# Temperature_Controller.net
KiCad netlist of a schematic drawn in Altium Designer
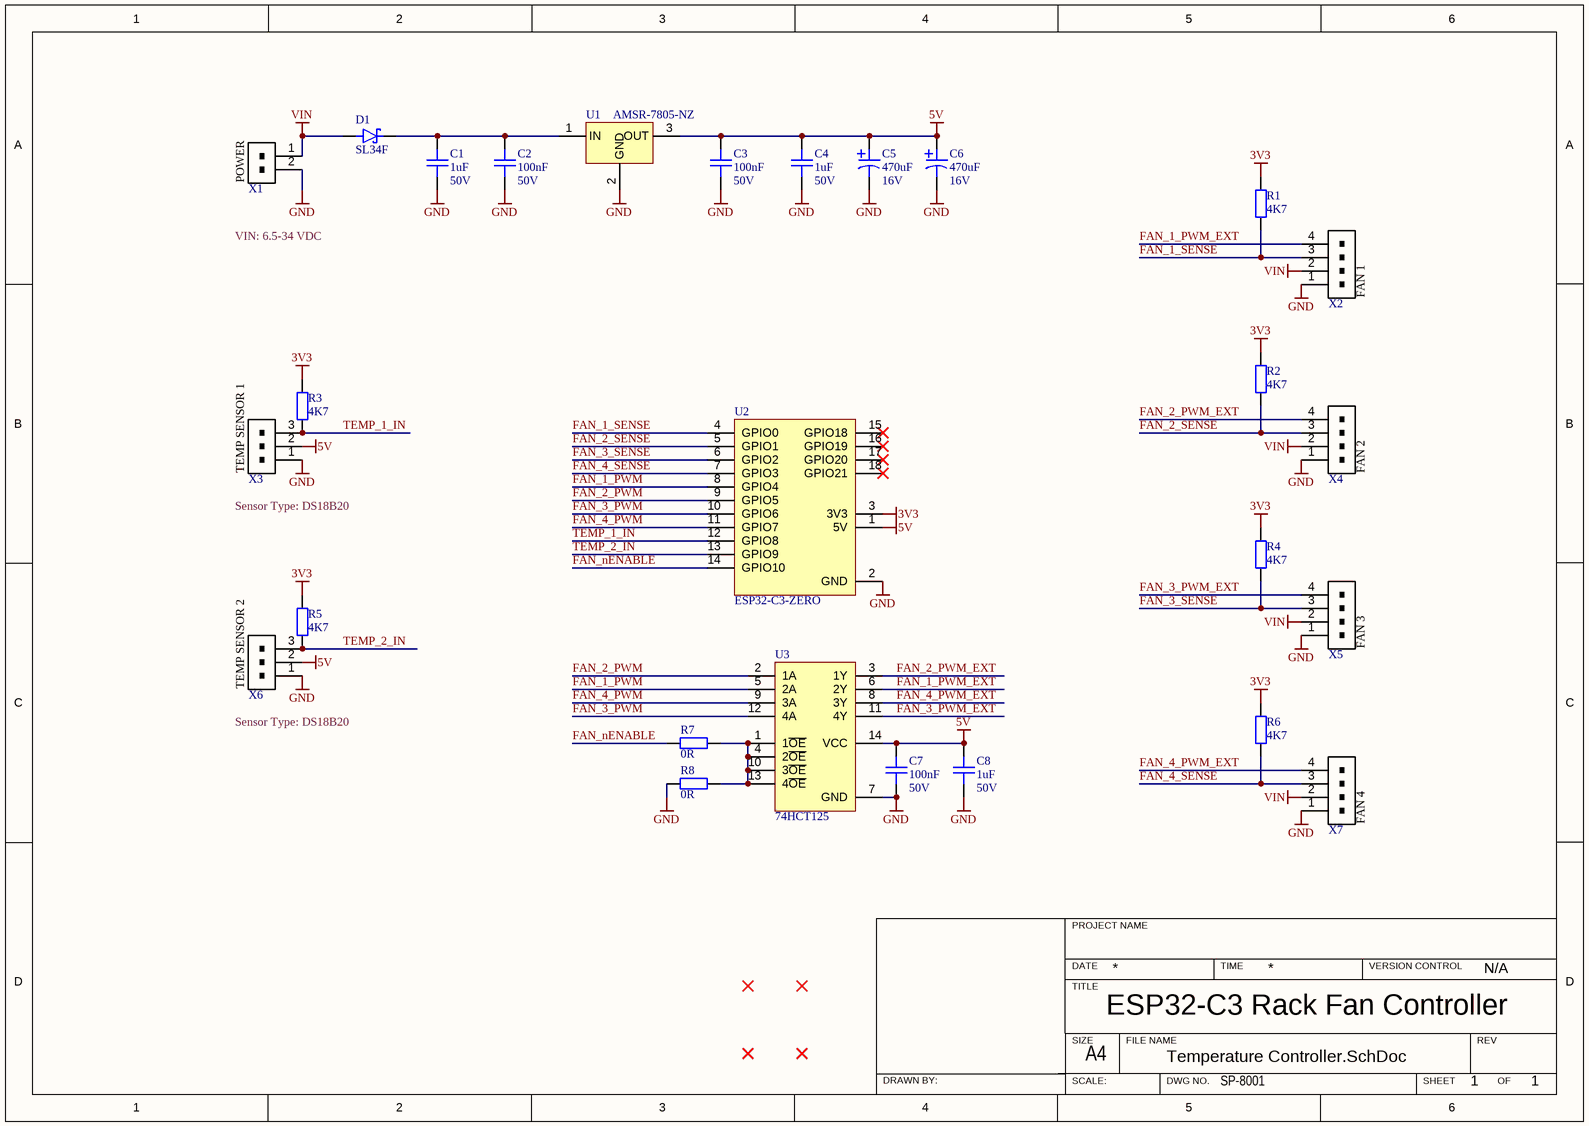
[diagram p0: Temperature Controller.SchDoc]

(export (version "E")
  (design (tool "Eeschema 10.0.6"))
  (components
    (comp (ref "C1")
      (value "1uF")
      (footprint "CAP-0805")
      (description "Capacitor Non-Polar")
      (fields (field (name "VOLTAGE") "50V") (field (name "TOLERANCE") "X7R"))
      (libsource (lib "ComponentDatabase") (part "CAP-0805"))
    )
    (comp (ref "C2")
      (value "100nF")
      (footprint "CAP-0805")
      (description "Capacitor Non-Polar")
      (fields (field (name "VOLTAGE") "50V") (field (name "TOLERANCE") "X7R"))
      (libsource (lib "ComponentDatabase") (part "CAP-0805"))
    )
    (comp (ref "C3")
      (value "100nF")
      (footprint "CAP-0805")
      (description "Capacitor Non-Polar")
      (fields (field (name "VOLTAGE") "50V") (field (name "TOLERANCE") "X7R"))
      (libsource (lib "ComponentDatabase") (part "CAP-0805"))
    )
    (comp (ref "C4")
      (value "1uF")
      (footprint "CAP-0805")
      (description "Capacitor Non-Polar")
      (fields (field (name "VOLTAGE") "50V") (field (name "TOLERANCE") "X7R"))
      (libsource (lib "ComponentDatabase") (part "CAP-0805"))
    )
    (comp (ref "C5")
      (value "470uF")
      (footprint "CAP-ELCO-SMD-FK1")
      (description "470uF 16V")
      (fields (field (name "VOLTAGE") "16V"))
      (libsource (lib "ComponentDatabase") (part "CAP-SMD-POL"))
    )
    (comp (ref "C6")
      (value "470uF")
      (footprint "CAP-ELCO-SMD-FK1")
      (description "470uF 16V")
      (fields (field (name "VOLTAGE") "16V"))
      (libsource (lib "ComponentDatabase") (part "CAP-SMD-POL"))
    )
    (comp (ref "C7")
      (value "100nF")
      (footprint "CAP-0805")
      (description "Capacitor Non-Polar")
      (fields (field (name "VOLTAGE") "50V") (field (name "TOLERANCE") "X7R"))
      (libsource (lib "ComponentDatabase") (part "CAP-0805"))
    )
    (comp (ref "C8")
      (value "1uF")
      (footprint "CAP-0805")
      (description "Capacitor Non-Polar")
      (fields (field (name "VOLTAGE") "50V") (field (name "TOLERANCE") "X7R"))
      (libsource (lib "ComponentDatabase") (part "CAP-0805"))
    )
    (comp (ref "D1")
      (value "SL34F")
      (footprint "D-SMAF")
      (description "3A 40V SCH.RECT. Vf=0.45V")
      (libsource (lib "ComponentDatabase") (part "D-SCHOTTKY"))
    )
    (comp (ref "MH1")
      (value "MECH-SCREW")
      (footprint "MECH-M3-LARGE-EMPTY-DOUBLE-SUPPORT")
      (description "M3, large ring, double support silkscreen")
      (libsource (lib "ComponentDatabase") (part "MECH-SCREW"))
    )
    (comp (ref "MH2")
      (value "MECH-SCREW")
      (footprint "MECH-M3-LARGE-EMPTY-DOUBLE-SUPPORT")
      (description "M3, large ring, double support silkscreen")
      (libsource (lib "ComponentDatabase") (part "MECH-SCREW"))
    )
    (comp (ref "MH3")
      (value "MECH-SCREW")
      (footprint "MECH-M3-LARGE-EMPTY-DOUBLE-SUPPORT")
      (description "M3, large ring, double support silkscreen")
      (libsource (lib "ComponentDatabase") (part "MECH-SCREW"))
    )
    (comp (ref "MH4")
      (value "MECH-SCREW")
      (footprint "MECH-M3-LARGE-EMPTY-DOUBLE-SUPPORT")
      (description "M3, large ring, double support silkscreen")
      (libsource (lib "ComponentDatabase") (part "MECH-SCREW"))
    )
    (comp (ref "R1")
      (value "4K7")
      (footprint "RES-0805")
      (description "Resistor")
      (libsource (lib "ComponentDatabase") (part "RES-0805"))
    )
    (comp (ref "R2")
      (value "4K7")
      (footprint "RES-0805")
      (description "Resistor")
      (libsource (lib "ComponentDatabase") (part "RES-0805"))
    )
    (comp (ref "R3")
      (value "4K7")
      (footprint "RES-0805")
      (description "Resistor")
      (libsource (lib "ComponentDatabase") (part "RES-0805"))
    )
    (comp (ref "R4")
      (value "4K7")
      (footprint "RES-0805")
      (description "Resistor")
      (libsource (lib "ComponentDatabase") (part "RES-0805"))
    )
    (comp (ref "R5")
      (value "4K7")
      (footprint "RES-0805")
      (description "Resistor")
      (libsource (lib "ComponentDatabase") (part "RES-0805"))
    )
    (comp (ref "R6")
      (value "4K7")
      (footprint "RES-0805")
      (description "Resistor")
      (libsource (lib "ComponentDatabase") (part "RES-0805"))
    )
    (comp (ref "R7")
      (value "0R")
      (footprint "RES-0805")
      (description "Resistor")
      (libsource (lib "") (part "RES-0805_1"))
    )
    (comp (ref "R8")
      (value "0R")
      (footprint "RES-0805")
      (description "Resistor")
      (libsource (lib "") (part "RES-0805_1"))
    )
    (comp (ref "U1")
      (value "AMSR-7805-NZ")
      (footprint "IC-AMS-7805")
      (description "Converter: DC/DC, 2.5W, Uin: 6.5-32V, Uout: 5VDC, Iout: 500mA")
      (libsource (lib "ComponentDatabase") (part "IC-LDO-AMSR-7805"))
    )
    (comp (ref "U2")
      (value "ESP32-C3-ZERO")
      (footprint "MOD-ESP32-C3-ZERO")
      (libsource (lib "ComponentDatabase") (part "MOD-ESP32-C3-ZERO"))
    )
    (comp (ref "U3")
      (value "74HCT125")
      (footprint "IC-SOIC-14")
      (description "QUADRUPLE BUS BUFFER GATES\nWITH 3-STATE OUTPUTS")
      (libsource (lib "ComponentDatabase") (part "IC-LOGIC-74HCT125"))
    )
    (comp (ref "X1")
      (value "CONN-2P")
      (footprint "CONN-2P-TERMINAL")
      (description "SORKAPOCS 2 P RM3.50 TL002V-02P (TLM) LIFTES 1.5qmm 10A 130V VDE")
      (libsource (lib "ComponentDatabase") (part "CONN-2P"))
    )
    (comp (ref "X2")
      (value "CONN-4P")
      (footprint "CONN-4P-NCW254")
      (description "TÁPCSATL. 2.54mm 4P APA 90° REVERSE NCW254-04RR (G-S) FORR.")
      (libsource (lib "ComponentDatabase") (part "CONN-4P"))
    )
    (comp (ref "X3")
      (value "CONN-3P")
      (footprint "CONN-3P-NCW254")
      (description "TÁPCSATL. 2.54mm 3P APA 90° REVERSE NCW254-03RR (G-S) FORR.")
      (libsource (lib "ComponentDatabase") (part "CONN-3P"))
    )
    (comp (ref "X4")
      (value "CONN-4P")
      (footprint "CONN-4P-NCW254")
      (description "TÁPCSATL. 2.54mm 4P APA 90° REVERSE NCW254-04RR (G-S) FORR.")
      (libsource (lib "ComponentDatabase") (part "CONN-4P"))
    )
    (comp (ref "X5")
      (value "CONN-4P")
      (footprint "CONN-4P-NCW254")
      (description "TÁPCSATL. 2.54mm 4P APA 90° REVERSE NCW254-04RR (G-S) FORR.")
      (libsource (lib "ComponentDatabase") (part "CONN-4P"))
    )
    (comp (ref "X6")
      (value "CONN-3P")
      (footprint "CONN-3P-NCW254")
      (description "TÁPCSATL. 2.54mm 3P APA 90° REVERSE NCW254-03RR (G-S) FORR.")
      (libsource (lib "ComponentDatabase") (part "CONN-3P"))
    )
    (comp (ref "X7")
      (value "CONN-4P")
      (footprint "CONN-4P-NCW254")
      (description "TÁPCSATL. 2.54mm 4P APA 90° REVERSE NCW254-04RR (G-S) FORR.")
      (libsource (lib "ComponentDatabase") (part "CONN-4P"))
    )
  )
  (nets
    (net (code "1") (name "/FAN_1_PWM") (class "Default")
      (node (ref "U2") (pin "8") (pinfunction "GPIO4_8") (pintype "passive"))
      (node (ref "U3") (pin "5") (pinfunction "2A_5") (pintype "passive"))
    )
    (net (code "2") (name "/FAN_1_PWM_EXT") (class "Default")
      (node (ref "U3") (pin "6") (pinfunction "2Y_6") (pintype "passive"))
      (node (ref "X2") (pin "4") (pinfunction "4_4") (pintype "passive"))
    )
    (net (code "3") (name "/FAN_1_SENSE") (class "Default")
      (node (ref "R1") (pin "1") (pinfunction "1_1") (pintype "passive"))
      (node (ref "U2") (pin "4") (pinfunction "GPIO0_4") (pintype "passive"))
      (node (ref "X2") (pin "3") (pinfunction "3_3") (pintype "passive"))
    )
    (net (code "4") (name "/FAN_2_PWM") (class "Default")
      (node (ref "U2") (pin "9") (pinfunction "GPIO5_9") (pintype "passive"))
      (node (ref "U3") (pin "2") (pinfunction "1A_2") (pintype "passive"))
    )
    (net (code "5") (name "/FAN_2_PWM_EXT") (class "Default")
      (node (ref "U3") (pin "3") (pinfunction "1Y_3") (pintype "passive"))
      (node (ref "X4") (pin "4") (pinfunction "4_4") (pintype "passive"))
    )
    (net (code "6") (name "/FAN_2_SENSE") (class "Default")
      (node (ref "R2") (pin "1") (pinfunction "1_1") (pintype "passive"))
      (node (ref "U2") (pin "5") (pinfunction "GPIO1_5") (pintype "passive"))
      (node (ref "X4") (pin "3") (pinfunction "3_3") (pintype "passive"))
    )
    (net (code "7") (name "/FAN_3_PWM") (class "Default")
      (node (ref "U2") (pin "10") (pinfunction "GPIO6_10") (pintype "passive"))
      (node (ref "U3") (pin "12") (pinfunction "4A_12") (pintype "passive"))
    )
    (net (code "8") (name "/FAN_3_PWM_EXT") (class "Default")
      (node (ref "U3") (pin "11") (pinfunction "4Y_11") (pintype "passive"))
      (node (ref "X5") (pin "4") (pinfunction "4_4") (pintype "passive"))
    )
    (net (code "9") (name "/FAN_3_SENSE") (class "Default")
      (node (ref "R4") (pin "1") (pinfunction "1_1") (pintype "passive"))
      (node (ref "U2") (pin "6") (pinfunction "GPIO2_6") (pintype "passive"))
      (node (ref "X5") (pin "3") (pinfunction "3_3") (pintype "passive"))
    )
    (net (code "10") (name "/FAN_4_PWM") (class "Default")
      (node (ref "U2") (pin "11") (pinfunction "GPIO7_11") (pintype "passive"))
      (node (ref "U3") (pin "9") (pinfunction "3A_9") (pintype "passive"))
    )
    (net (code "11") (name "/FAN_4_PWM_EXT") (class "Default")
      (node (ref "U3") (pin "8") (pinfunction "3Y_8") (pintype "passive"))
      (node (ref "X7") (pin "4") (pinfunction "4_4") (pintype "passive"))
    )
    (net (code "12") (name "/FAN_4_SENSE") (class "Default")
      (node (ref "R6") (pin "1") (pinfunction "1_1") (pintype "passive"))
      (node (ref "U2") (pin "7") (pinfunction "GPIO3_7") (pintype "passive"))
      (node (ref "X7") (pin "3") (pinfunction "3_3") (pintype "passive"))
    )
    (net (code "13") (name "/FAN_nENABLE") (class "Default")
      (node (ref "R7") (pin "1") (pinfunction "1_1") (pintype "passive"))
      (node (ref "U2") (pin "14") (pinfunction "GPIO10_14") (pintype "passive"))
    )
    (net (code "14") (name "/TEMP_1_IN") (class "Default")
      (node (ref "R3") (pin "1") (pinfunction "1_1") (pintype "passive"))
      (node (ref "U2") (pin "12") (pinfunction "GPIO8_12") (pintype "passive"))
      (node (ref "X3") (pin "3") (pinfunction "3_3") (pintype "passive"))
    )
    (net (code "15") (name "/TEMP_2_IN") (class "Default")
      (node (ref "R5") (pin "1") (pinfunction "1_1") (pintype "passive"))
      (node (ref "U2") (pin "13") (pinfunction "GPIO9_13") (pintype "passive"))
      (node (ref "X6") (pin "3") (pinfunction "3_3") (pintype "passive"))
    )
    (net (code "16") (name "3V3") (class "Default")
      (node (ref "R1") (pin "2") (pinfunction "2_2") (pintype "passive"))
      (node (ref "R2") (pin "2") (pinfunction "2_2") (pintype "passive"))
      (node (ref "R3") (pin "2") (pinfunction "2_2") (pintype "passive"))
      (node (ref "R4") (pin "2") (pinfunction "2_2") (pintype "passive"))
      (node (ref "R5") (pin "2") (pinfunction "2_2") (pintype "passive"))
      (node (ref "R6") (pin "2") (pinfunction "2_2") (pintype "passive"))
      (node (ref "U2") (pin "3") (pinfunction "3V3_3") (pintype "passive"))
    )
    (net (code "17") (name "5V") (class "Default")
      (node (ref "C3") (pin "2") (pinfunction "2_2") (pintype "passive"))
      (node (ref "C4") (pin "2") (pinfunction "2_2") (pintype "passive"))
      (node (ref "C5") (pin "2") (pinfunction "2_2") (pintype "passive"))
      (node (ref "C6") (pin "2") (pinfunction "2_2") (pintype "passive"))
      (node (ref "C7") (pin "2") (pinfunction "2_2") (pintype "passive"))
      (node (ref "C8") (pin "2") (pinfunction "2_2") (pintype "passive"))
      (node (ref "U1") (pin "3") (pinfunction "OUT_3") (pintype "passive"))
      (node (ref "U2") (pin "1") (pinfunction "5V_1") (pintype "passive"))
      (node (ref "U3") (pin "14") (pinfunction "VCC_14") (pintype "passive"))
      (node (ref "X3") (pin "2") (pinfunction "2_2") (pintype "passive"))
      (node (ref "X6") (pin "2") (pinfunction "2_2") (pintype "passive"))
    )
    (net (code "18") (name "GND") (class "Default")
      (node (ref "C1") (pin "1") (pinfunction "1_1") (pintype "passive"))
      (node (ref "C2") (pin "1") (pinfunction "1_1") (pintype "passive"))
      (node (ref "C3") (pin "1") (pinfunction "1_1") (pintype "passive"))
      (node (ref "C4") (pin "1") (pinfunction "1_1") (pintype "passive"))
      (node (ref "C5") (pin "1") (pinfunction "1_1") (pintype "passive"))
      (node (ref "C6") (pin "1") (pinfunction "1_1") (pintype "passive"))
      (node (ref "C7") (pin "1") (pinfunction "1_1") (pintype "passive"))
      (node (ref "C8") (pin "1") (pinfunction "1_1") (pintype "passive"))
      (node (ref "R8") (pin "1") (pinfunction "1_1") (pintype "passive"))
      (node (ref "U1") (pin "2") (pinfunction "GND_2") (pintype "passive"))
      (node (ref "U2") (pin "2") (pinfunction "GND_2") (pintype "passive"))
      (node (ref "U3") (pin "7") (pinfunction "GND_7") (pintype "passive"))
      (node (ref "X1") (pin "2") (pinfunction "2_2") (pintype "passive"))
      (node (ref "X2") (pin "1") (pinfunction "1_1") (pintype "passive"))
      (node (ref "X3") (pin "1") (pinfunction "1_1") (pintype "passive"))
      (node (ref "X4") (pin "1") (pinfunction "1_1") (pintype "passive"))
      (node (ref "X5") (pin "1") (pinfunction "1_1") (pintype "passive"))
      (node (ref "X6") (pin "1") (pinfunction "1_1") (pintype "passive"))
      (node (ref "X7") (pin "1") (pinfunction "1_1") (pintype "passive"))
    )
    (net (code "19") (name "Net-(U1-IN)") (class "Default")
      (node (ref "C1") (pin "2") (pinfunction "2_2") (pintype "passive"))
      (node (ref "C2") (pin "2") (pinfunction "2_2") (pintype "passive"))
      (node (ref "D1") (pin "K") (pinfunction "K_K") (pintype "passive"))
      (node (ref "U1") (pin "1") (pinfunction "IN_1") (pintype "passive"))
    )
    (net (code "20") (name "Net-(U3-1~{OE})") (class "Default")
      (node (ref "R7") (pin "2") (pinfunction "2_2") (pintype "passive"))
      (node (ref "R8") (pin "2") (pinfunction "2_2") (pintype "passive"))
      (node (ref "U3") (pin "1") (pinfunction "1~{OE}_1") (pintype "passive"))
      (node (ref "U3") (pin "10") (pinfunction "3~{OE}_10") (pintype "passive"))
      (node (ref "U3") (pin "13") (pinfunction "4~{OE}_13") (pintype "passive"))
      (node (ref "U3") (pin "4") (pinfunction "2~{OE}_4") (pintype "passive"))
    )
    (net (code "21") (name "VIN") (class "Default")
      (node (ref "D1") (pin "A") (pinfunction "A_A") (pintype "passive"))
      (node (ref "X1") (pin "1") (pinfunction "1_1") (pintype "passive"))
      (node (ref "X2") (pin "2") (pinfunction "2_2") (pintype "passive"))
      (node (ref "X4") (pin "2") (pinfunction "2_2") (pintype "passive"))
      (node (ref "X5") (pin "2") (pinfunction "2_2") (pintype "passive"))
      (node (ref "X7") (pin "2") (pinfunction "2_2") (pintype "passive"))
    )
    (net (code "22") (name "unconnected-(MH1-Con-PadMH)") (class "Default")
      (node (ref "MH1") (pin "MH") (pinfunction "Con_MH") (pintype "passive+no_connect"))
    )
    (net (code "23") (name "unconnected-(MH2-Con-PadMH)") (class "Default")
      (node (ref "MH2") (pin "MH") (pinfunction "Con_MH") (pintype "passive+no_connect"))
    )
    (net (code "24") (name "unconnected-(MH3-Con-PadMH)") (class "Default")
      (node (ref "MH3") (pin "MH") (pinfunction "Con_MH") (pintype "passive+no_connect"))
    )
    (net (code "25") (name "unconnected-(MH4-Con-PadMH)") (class "Default")
      (node (ref "MH4") (pin "MH") (pinfunction "Con_MH") (pintype "passive+no_connect"))
    )
    (net (code "26") (name "unconnected-(U2-GPIO18-Pad15)") (class "Default")
      (node (ref "U2") (pin "15") (pinfunction "GPIO18_15") (pintype "passive+no_connect"))
    )
    (net (code "27") (name "unconnected-(U2-GPIO19-Pad16)") (class "Default")
      (node (ref "U2") (pin "16") (pinfunction "GPIO19_16") (pintype "passive+no_connect"))
    )
    (net (code "28") (name "unconnected-(U2-GPIO20-Pad17)") (class "Default")
      (node (ref "U2") (pin "17") (pinfunction "GPIO20_17") (pintype "passive+no_connect"))
    )
    (net (code "29") (name "unconnected-(U2-GPIO21-Pad18)") (class "Default")
      (node (ref "U2") (pin "18") (pinfunction "GPIO21_18") (pintype "passive+no_connect"))
    )
  )
)
